# TSOC_GROVEY_WIFI_R1_0.net
KiCad netlist of a schematic drawn in EAGLE
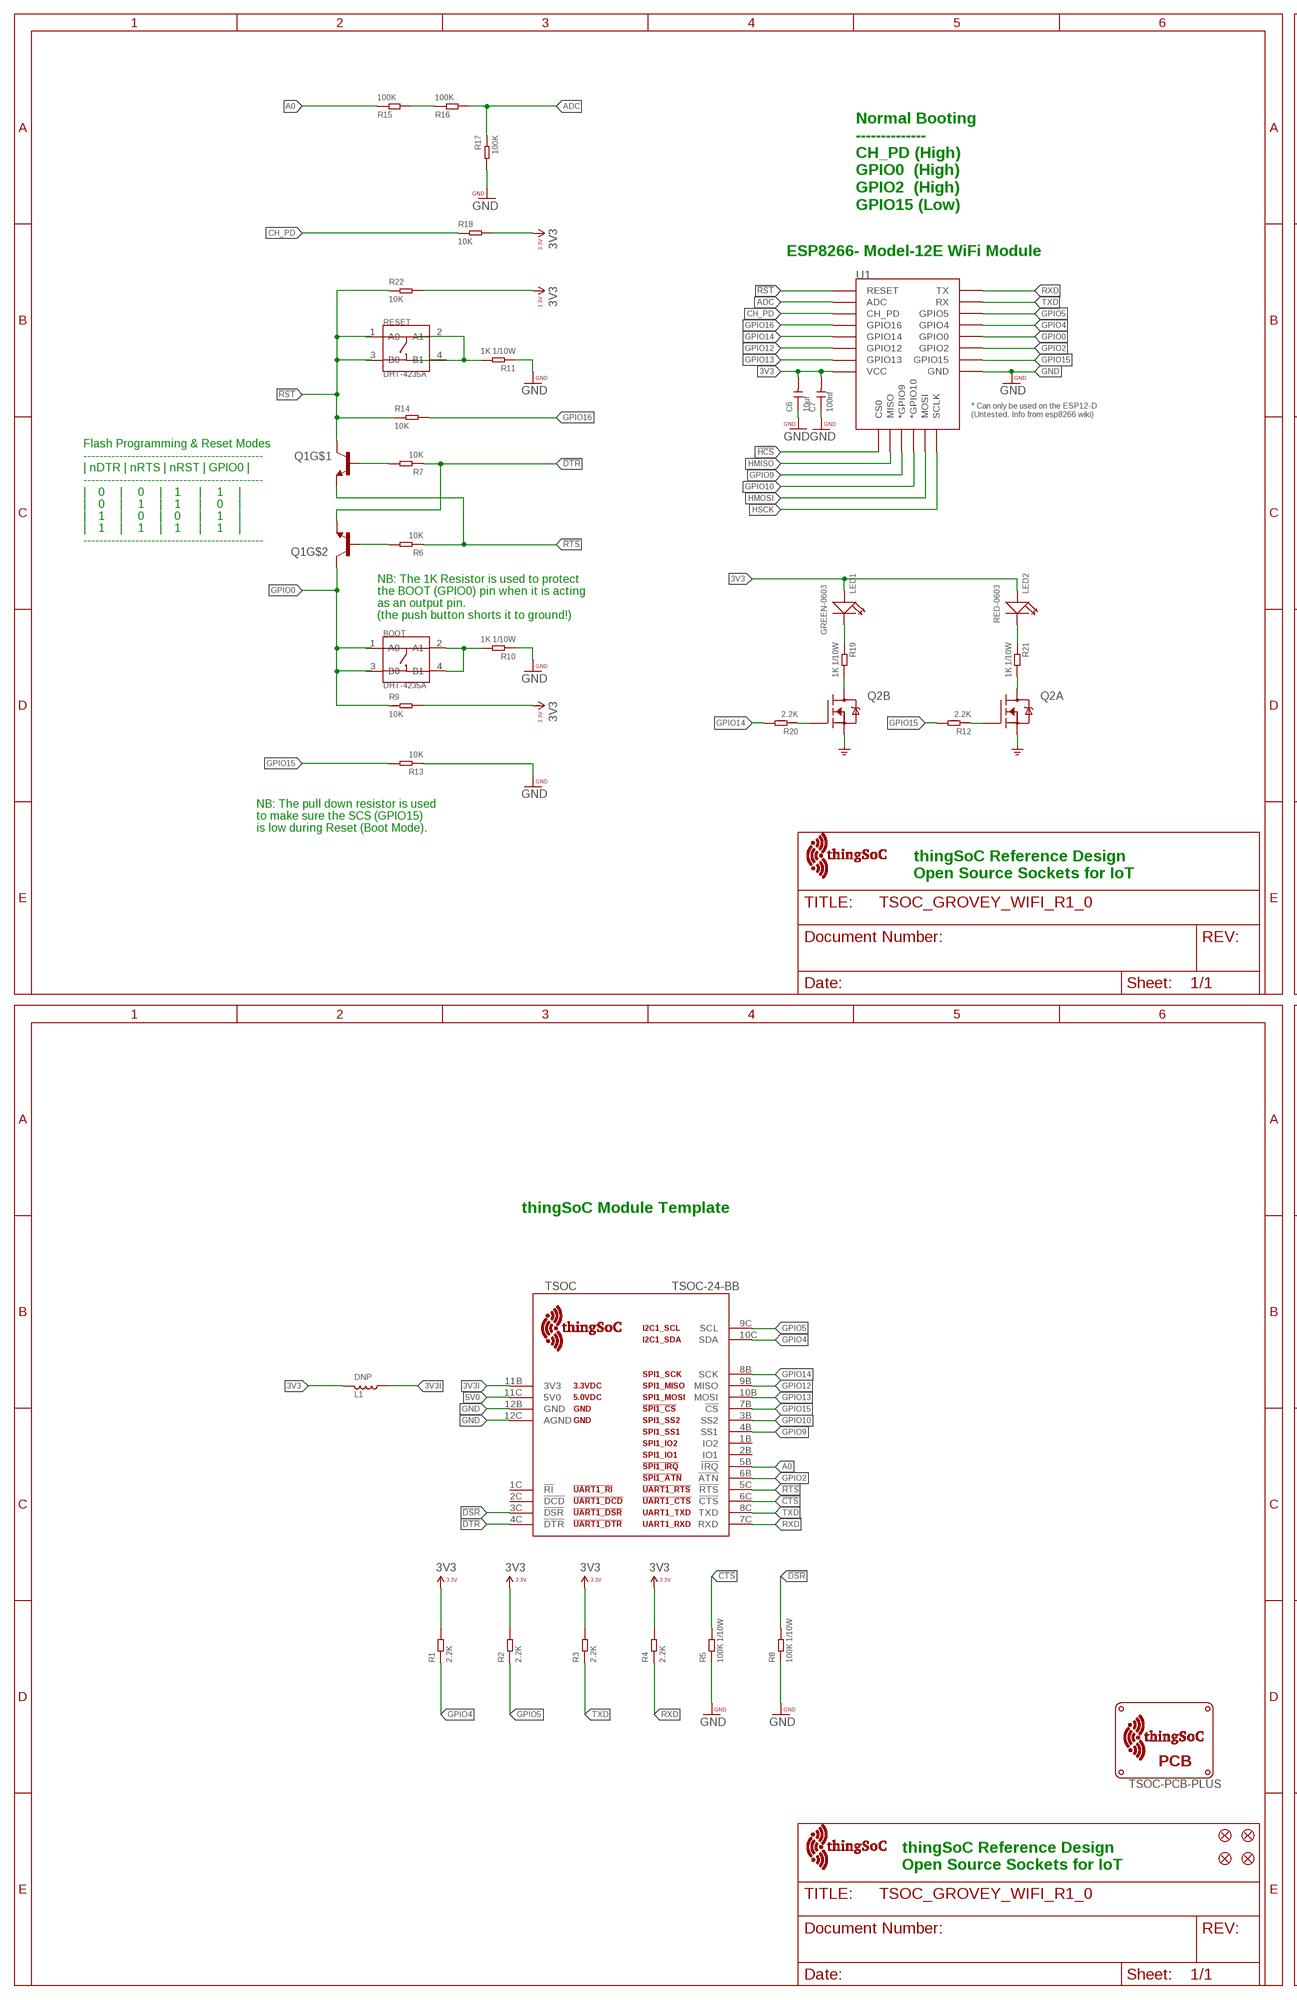
[diagram p0: schematic, sheet 1, part 1 of 2]
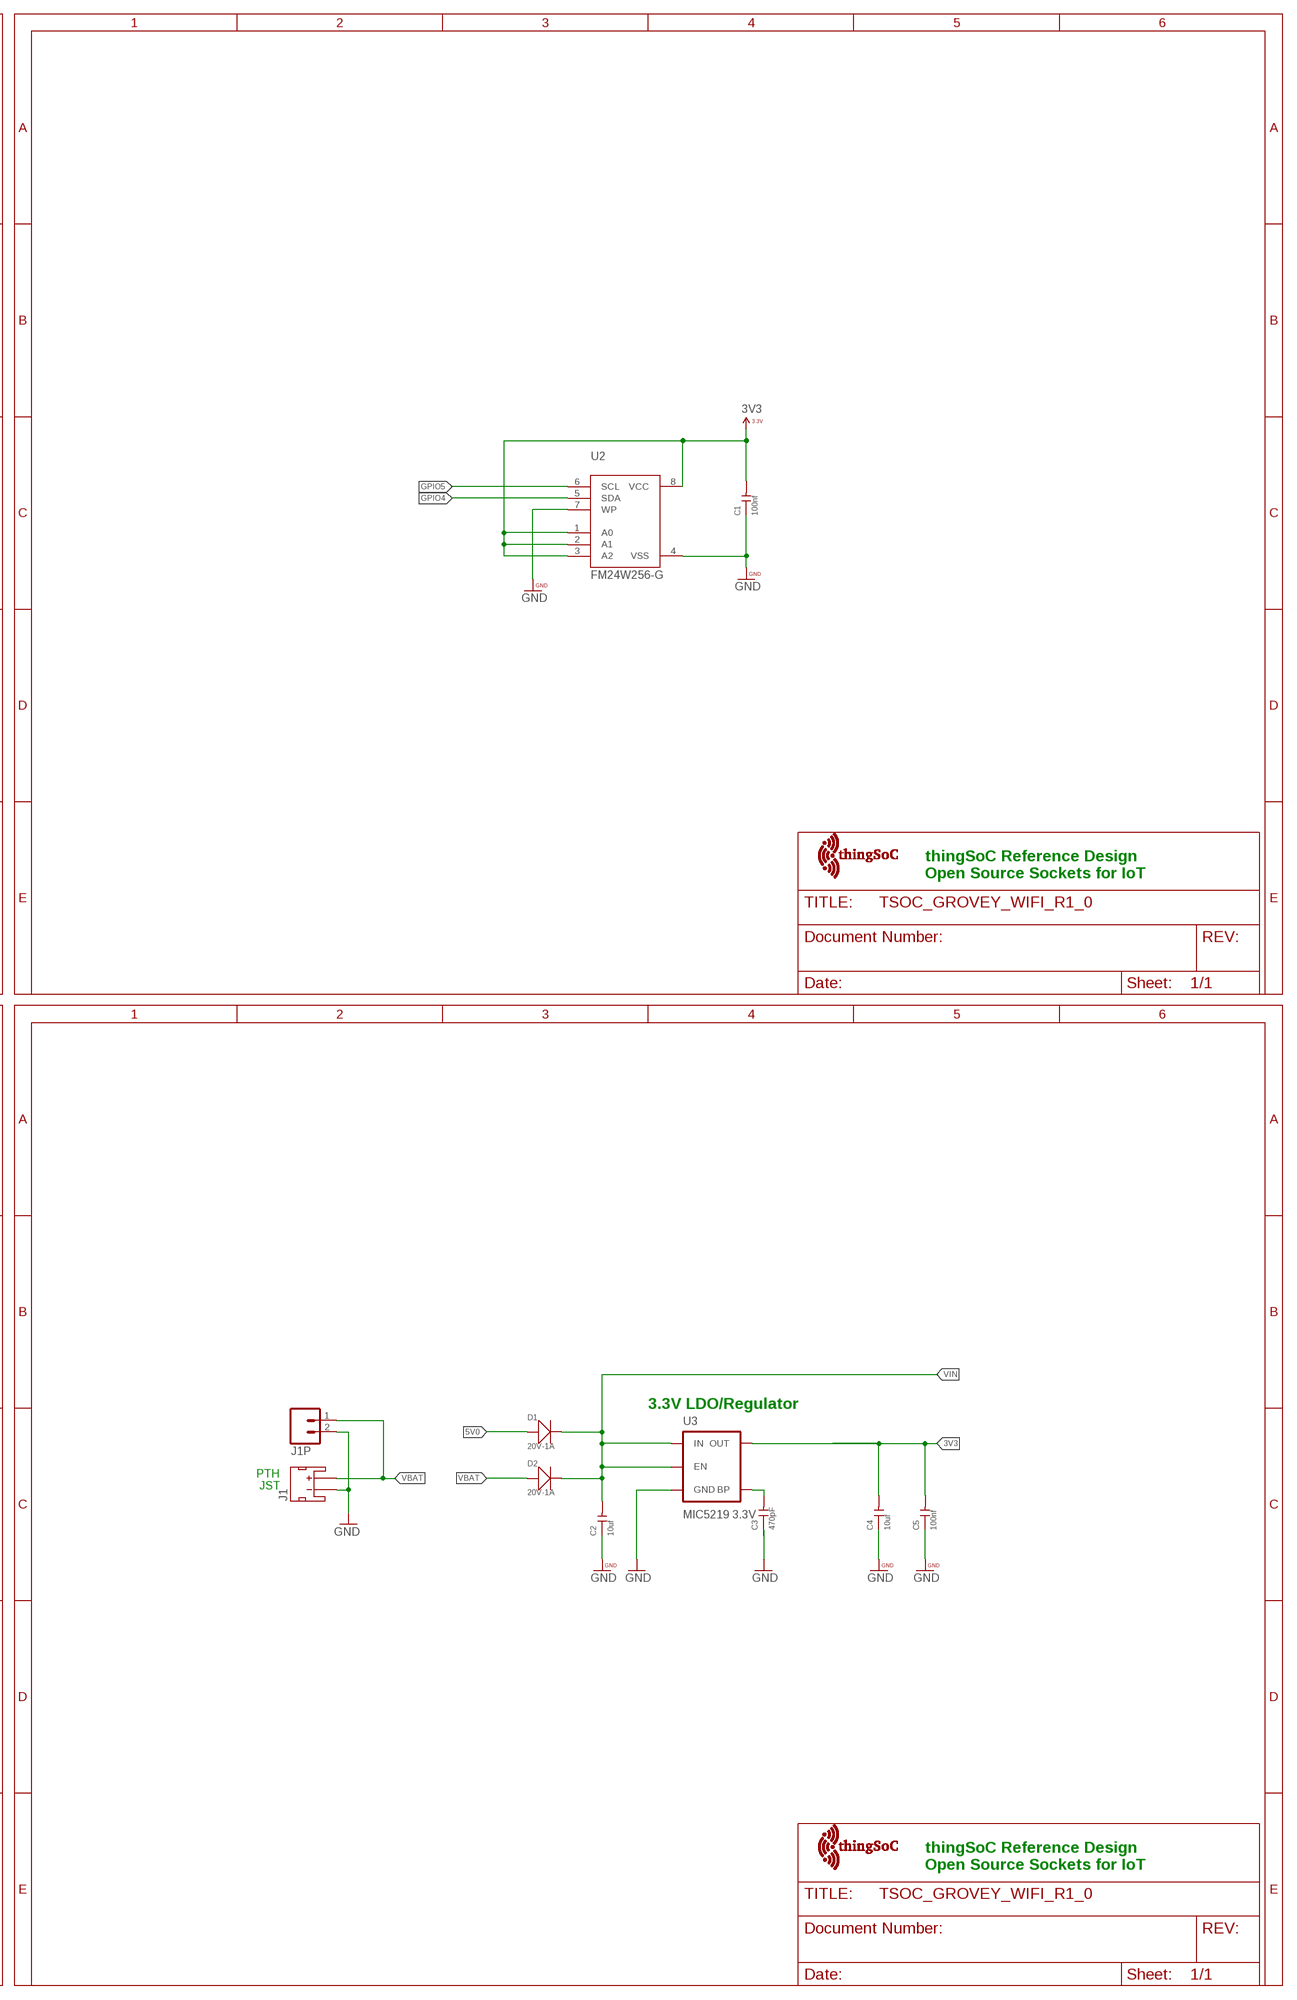
[diagram p1: schematic, sheet 1, part 2 of 2]

(export (version "E")
  (design (tool "Eeschema 10.0.6"))
  (components
    (comp (ref "$$U$1")
      (value "TSOC-LOGO-MED")
      (footprint "eagle-import:TSOC-LOGO-MED")
      (libsource (lib "eagle-import") (part "TSOC-LOGO-MED"))
    )
    (comp (ref "$$U$2")
      (value "TSOC-LOGO-MED")
      (footprint "eagle-import:TSOC-LOGO-MED")
      (libsource (lib "eagle-import") (part "TSOC-LOGO-MED"))
    )
    (comp (ref "BOOT")
      (value "DHT-4235A")
      (footprint "eagle-import:SW4-SMD-4.2X3.2X2.5MM")
      (libsource (lib "eagle-import") (part "SMD-BUTTON-TOP-DHT-4235A(4P-4.2X3.2MM)"))
    )
    (comp (ref "C1")
      (value "100nf")
      (footprint "eagle-import:C0603")
      (fields (field (name "MPN") "CC0603KRX7R9BB104"))
      (libsource (lib "eagle-import") (part "CERAMIC-100NF-50V-10%-X7R(0603)"))
    )
    (comp (ref "C2")
      (value "10uf")
      (footprint "eagle-import:C1206")
      (fields (field (name "MPN") "CC1206KKX5R8BB106"))
      (libsource (lib "eagle-import") (part "CERAMIC-10UF-25V-10%-X5R(1206)"))
    )
    (comp (ref "C3")
      (value "470pF")
      (footprint "eagle-import:C0603")
      (fields (field (name "MPN") "CC0603KRX7R9BB104"))
      (libsource (lib "eagle-import") (part "CERAMIC-100NF-50V-10%-X7R(0603)"))
    )
    (comp (ref "C4")
      (value "10uf")
      (footprint "eagle-import:C1206")
      (fields (field (name "MPN") "CC1206KKX5R8BB106"))
      (libsource (lib "eagle-import") (part "CERAMIC-10UF-25V-10%-X5R(1206)"))
    )
    (comp (ref "C5")
      (value "100nf")
      (footprint "eagle-import:C0603")
      (fields (field (name "MPN") "CC0603KRX7R9BB104"))
      (libsource (lib "eagle-import") (part "CERAMIC-100NF-50V-10%-X7R(0603)"))
    )
    (comp (ref "C6")
      (value "10uf")
      (footprint "eagle-import:C1206")
      (fields (field (name "MPN") "CC1206KKX5R8BB106"))
      (libsource (lib "eagle-import") (part "CERAMIC-10UF-25V-10%-X5R(1206)"))
    )
    (comp (ref "C7")
      (value "100nf")
      (footprint "eagle-import:C0603")
      (fields (field (name "MPN") "CC0603KRX7R9BB104"))
      (libsource (lib "eagle-import") (part "CERAMIC-100NF-50V-10%-X7R(0603)"))
    )
    (comp (ref "D1")
      (value "20V-1A")
      (footprint "eagle-import:SOD-123")
      (fields (field (name "MPN") "B5819W"))
      (libsource (lib "eagle-import") (part "SMD-DIODE-SCHOTTKY-20V-1A(SOD-123)"))
    )
    (comp (ref "D2")
      (value "20V-1A")
      (footprint "eagle-import:SOD-123")
      (fields (field (name "MPN") "B5819W"))
      (libsource (lib "eagle-import") (part "SMD-DIODE-SCHOTTKY-20V-1A(SOD-123)"))
    )
    (comp (ref "FID1")
      (value "FIDUCIALUFIDUCIAL")
      (footprint "eagle-import:MICRO-FIDUCIAL")
      (libsource (lib "eagle-import") (part "FIDUCIALUFIDUCIAL"))
    )
    (comp (ref "FID2")
      (value "FIDUCIALUFIDUCIAL")
      (footprint "eagle-import:MICRO-FIDUCIAL")
      (libsource (lib "eagle-import") (part "FIDUCIALUFIDUCIAL"))
    )
    (comp (ref "FID3")
      (value "FIDUCIALUFIDUCIAL")
      (footprint "eagle-import:MICRO-FIDUCIAL")
      (libsource (lib "eagle-import") (part "FIDUCIALUFIDUCIAL"))
    )
    (comp (ref "FID4")
      (value "FIDUCIALUFIDUCIAL")
      (footprint "eagle-import:MICRO-FIDUCIAL")
      (libsource (lib "eagle-import") (part "FIDUCIALUFIDUCIAL"))
    )
    (comp (ref "J1")
      (value "JST_2MM_MALE")
      (footprint "eagle-import:JST-2-SMD")
      (libsource (lib "eagle-import") (part "JST_2MM_MALE"))
    )
    (comp (ref "J1P")
      (value "M02-JST-2-PTH-NO_SILK")
      (footprint "eagle-import:JST-2-PTH-NS")
      (libsource (lib "eagle-import") (part "M02-JST-2-PTH-NO_SILK"))
    )
    (comp (ref "L1")
      (value "DNP")
      (footprint "eagle-import:L0603")
      (fields (field (name "MPN") "BLM18AG121SN1D"))
      (libsource (lib "eagle-import") (part "SMD-FERRITE-CHIP-120-OHM-500MA(0603)"))
    )
    (comp (ref "LED1")
      (value "GREEN-0603")
      (footprint "eagle-import:LED-0603")
      (fields (field (name "MPN") "19-217-G7C-AN1P2-3T"))
      (libsource (lib "eagle-import") (part "SMD-LED-CLEAR-GREEN(0603)"))
    )
    (comp (ref "LED2")
      (value "RED-0603")
      (footprint "eagle-import:LED-0603")
      (fields (field (name "MPN") "19-217-R6C-AL1M2VY-3T"))
      (libsource (lib "eagle-import") (part "LED-SMD-RED-DIFFUSED(0603)"))
    )
    (comp (ref "PCB")
      (value "TSOC-PCB-PLUS")
      (footprint "eagle-import:TSOC-BB-BRD-PLUS-DIM")
      (libsource (lib "eagle-import") (part "TSOC-PCB-PLUS"))
    )
    (comp (ref "Q1")
      (value "MMBT2222A")
      (footprint "eagle-import:SOT363")
      (libsource (lib "eagle-import") (part "MMDT3904"))
    )
    (comp (ref "Q2")
      (value "FDG1024NZ")
      (footprint "eagle-import:SOT95P280X110-6N")
      (libsource (lib "eagle-import") (part "FDG1024NZ"))
    )
    (comp (ref "R1")
      (value "2.2K")
      (footprint "eagle-import:R0603")
      (fields (field (name "MPN") "RC0603JR-072K2L"))
      (libsource (lib "eagle-import") (part "SMD-RES-2.2K-5%-1/10W(0603)"))
    )
    (comp (ref "R2")
      (value "2.2K")
      (footprint "eagle-import:R0603")
      (fields (field (name "MPN") "RC0603JR-072K2L"))
      (libsource (lib "eagle-import") (part "SMD-RES-2.2K-5%-1/10W(0603)"))
    )
    (comp (ref "R3")
      (value "2.2K")
      (footprint "eagle-import:R0603")
      (fields (field (name "MPN") "RC0603JR-072K2L"))
      (libsource (lib "eagle-import") (part "SMD-RES-2.2K-5%-1/10W(0603)"))
    )
    (comp (ref "R4")
      (value "2.2K")
      (footprint "eagle-import:R0603")
      (fields (field (name "MPN") "RC0603JR-072K2L"))
      (libsource (lib "eagle-import") (part "SMD-RES-2.2K-5%-1/10W(0603)"))
    )
    (comp (ref "R5")
      (value "100K 1/10W")
      (footprint "eagle-import:R0603")
      (fields (field (name "MPN") "RC0603JR-07100KL"))
      (libsource (lib "eagle-import") (part "SMD-RES-100K-5%-1/10W(0603)"))
    )
    (comp (ref "R6")
      (value "10K")
      (footprint "eagle-import:R0603")
      (fields (field (name "MPN") "RC0603FR-0710KL"))
      (libsource (lib "eagle-import") (part "SMD-RES-10K-1%-1/10W(0603)"))
    )
    (comp (ref "R7")
      (value "10K")
      (footprint "eagle-import:R0603")
      (fields (field (name "MPN") "RC0603FR-0710KL"))
      (libsource (lib "eagle-import") (part "SMD-RES-10K-1%-1/10W(0603)"))
    )
    (comp (ref "R8")
      (value "100K 1/10W")
      (footprint "eagle-import:R0603")
      (fields (field (name "MPN") "RC0603JR-07100KL"))
      (libsource (lib "eagle-import") (part "SMD-RES-100K-5%-1/10W(0603)"))
    )
    (comp (ref "R9")
      (value "10K")
      (footprint "eagle-import:R0603")
      (fields (field (name "MPN") "RC0603FR-0710KL"))
      (libsource (lib "eagle-import") (part "SMD-RES-10K-1%-1/10W(0603)"))
    )
    (comp (ref "R10")
      (value "1K 1/10W")
      (footprint "eagle-import:R0603")
      (fields (field (name "MPN") "RC0603JR-071KL"))
      (libsource (lib "eagle-import") (part "SMD-RES-1K-5%-1/10W(0603)"))
    )
    (comp (ref "R11")
      (value "1K 1/10W")
      (footprint "eagle-import:R0603")
      (fields (field (name "MPN") "RC0603JR-071KL"))
      (libsource (lib "eagle-import") (part "SMD-RES-1K-5%-1/10W(0603)"))
    )
    (comp (ref "R12")
      (value "2.2K")
      (footprint "eagle-import:R0603")
      (fields (field (name "MPN") "RC0603JR-072K2L"))
      (libsource (lib "eagle-import") (part "SMD-RES-2.2K-5%-1/10W(0603)"))
    )
    (comp (ref "R13")
      (value "10K")
      (footprint "eagle-import:R0603")
      (fields (field (name "MPN") "RC0603FR-0710KL"))
      (libsource (lib "eagle-import") (part "SMD-RES-10K-1%-1/10W(0603)"))
    )
    (comp (ref "R14")
      (value "10K")
      (footprint "eagle-import:R0603")
      (fields (field (name "MPN") "RC0603FR-0710KL"))
      (libsource (lib "eagle-import") (part "SMD-RES-10K-1%-1/10W(0603)"))
    )
    (comp (ref "R15")
      (value "100K")
      (footprint "eagle-import:R0603")
      (fields (field (name "MPN") "RC0603FR-07100KL"))
      (libsource (lib "eagle-import") (part "SMD-RES-100K-1%-1/10W(0603)"))
    )
    (comp (ref "R16")
      (value "100K")
      (footprint "eagle-import:R0603")
      (fields (field (name "MPN") "RC0603FR-07100KL"))
      (libsource (lib "eagle-import") (part "SMD-RES-100K-1%-1/10W(0603)"))
    )
    (comp (ref "R17")
      (value "100K")
      (footprint "eagle-import:R0603")
      (fields (field (name "MPN") "RC0603FR-07100KL"))
      (libsource (lib "eagle-import") (part "SMD-RES-100K-1%-1/10W(0603)"))
    )
    (comp (ref "R18")
      (value "10K")
      (footprint "eagle-import:R0603")
      (fields (field (name "MPN") "RC0603FR-0710KL"))
      (libsource (lib "eagle-import") (part "SMD-RES-10K-1%-1/10W(0603)"))
    )
    (comp (ref "R19")
      (value "1K 1/10W")
      (footprint "eagle-import:R0603")
      (fields (field (name "MPN") "RC0603JR-071KL"))
      (libsource (lib "eagle-import") (part "SMD-RES-1K-5%-1/10W(0603)"))
    )
    (comp (ref "R20")
      (value "2.2K")
      (footprint "eagle-import:R0603")
      (fields (field (name "MPN") "RC0603JR-072K2L"))
      (libsource (lib "eagle-import") (part "SMD-RES-2.2K-5%-1/10W(0603)"))
    )
    (comp (ref "R21")
      (value "1K 1/10W")
      (footprint "eagle-import:R0603")
      (fields (field (name "MPN") "RC0603JR-071KL"))
      (libsource (lib "eagle-import") (part "SMD-RES-1K-5%-1/10W(0603)"))
    )
    (comp (ref "R22")
      (value "10K")
      (footprint "eagle-import:R0603")
      (fields (field (name "MPN") "RC0603FR-0710KL"))
      (libsource (lib "eagle-import") (part "SMD-RES-10K-1%-1/10W(0603)"))
    )
    (comp (ref "RESET")
      (value "DHT-4235A")
      (footprint "eagle-import:SW4-SMD-4.2X3.2X2.5MM")
      (libsource (lib "eagle-import") (part "SMD-BUTTON-TOP-DHT-4235A(4P-4.2X3.2MM)"))
    )
    (comp (ref "TSOC")
      (value "TSOC-24-BB")
      (footprint "eagle-import:TSOC-BB-S24")
      (libsource (lib "eagle-import") (part "TSOC-24-BB"))
    )
    (comp (ref "U$101")
      (value "TSOC-LOGO-MED")
      (footprint "eagle-import:TSOC-LOGO-MED")
      (libsource (lib "eagle-import") (part "TSOC-LOGO-MED"))
    )
    (comp (ref "U$102")
      (value "TSOC-LOGO-MED")
      (footprint "eagle-import:TSOC-LOGO-MED")
      (libsource (lib "eagle-import") (part "TSOC-LOGO-MED"))
    )
    (comp (ref "U1")
      (value "ESP12ESMD")
      (footprint "eagle-import:ESP12E-SMD")
      (libsource (lib "eagle-import") (part "ESP12ESMD"))
    )
    (comp (ref "U2")
      (value "FM24W256-G")
      (footprint "eagle-import:SO08")
      (libsource (lib "eagle-import") (part "FM24W256-G"))
    )
    (comp (ref "U3")
      (value "MIC5219 3.3V")
      (footprint "eagle-import:SOT23-5")
      (libsource (lib "eagle-import") (part "V_REG_MIC52193.3V"))
    )
  )
  (nets
    (net (code "1") (name "/~{CTS}") (class "Default")
      (node (ref "R5") (pin "2") (pinfunction "2_2") (pintype "passive"))
      (node (ref "TSOC") (pin "6C") (pinfunction "~{CTS}_6C") (pintype "bidirectional"))
    )
    (net (code "2") (name "/~{DSR}") (class "Default")
      (node (ref "R8") (pin "2") (pinfunction "2_2") (pintype "passive"))
      (node (ref "TSOC") (pin "3C") (pinfunction "~{DSR}_3C") (pintype "bidirectional"))
    )
    (net (code "3") (name "/~{DTR}") (class "Default")
      (node (ref "Q1") (pin "1") (pinfunction "E_1") (pintype "passive"))
      (node (ref "R7") (pin "1") (pinfunction "1_1") (pintype "passive"))
      (node (ref "TSOC") (pin "4C") (pinfunction "~{DTR}_4C") (pintype "bidirectional"))
    )
    (net (code "4") (name "/~{HCS}") (class "Default")
      (node (ref "U1") (pin "CS0") (pinfunction "CS0_CS0") (pintype "bidirectional"))
    )
    (net (code "5") (name "/~{RST}") (class "Default")
      (node (ref "Q1") (pin "3") (pinfunction "C_3") (pintype "passive"))
      (node (ref "R14") (pin "1") (pinfunction "1_1") (pintype "passive"))
      (node (ref "R22") (pin "1") (pinfunction "1_1") (pintype "passive"))
      (node (ref "RESET") (pin "1") (pinfunction "A0_1") (pintype "bidirectional"))
      (node (ref "RESET") (pin "3") (pinfunction "B0_3") (pintype "bidirectional"))
      (node (ref "U1") (pin "RESET") (pinfunction "RESET_RESET") (pintype "bidirectional"))
    )
    (net (code "6") (name "/~{RTS}") (class "Default")
      (node (ref "Q1") (pin "4") (pinfunction "E_4") (pintype "passive"))
      (node (ref "R6") (pin "1") (pinfunction "1_1") (pintype "passive"))
      (node (ref "TSOC") (pin "5C") (pinfunction "~{RTS}_5C") (pintype "bidirectional"))
    )
    (net (code "7") (name "3V3") (class "Default")
      (node (ref "C1") (pin "2") (pinfunction "2_2") (pintype "passive"))
      (node (ref "C4") (pin "2") (pinfunction "2_2") (pintype "passive"))
      (node (ref "C5") (pin "2") (pinfunction "2_2") (pintype "passive"))
      (node (ref "C6") (pin "2") (pinfunction "2_2") (pintype "passive"))
      (node (ref "C7") (pin "2") (pinfunction "2_2") (pintype "passive"))
      (node (ref "L1") (pin "1") (pinfunction "1_1") (pintype "passive"))
      (node (ref "LED1") (pin "+") (pinfunction "+_+") (pintype "passive"))
      (node (ref "LED2") (pin "+") (pinfunction "+_+") (pintype "passive"))
      (node (ref "R1") (pin "2") (pinfunction "2_2") (pintype "passive"))
      (node (ref "R18") (pin "2") (pinfunction "2_2") (pintype "passive"))
      (node (ref "R2") (pin "2") (pinfunction "2_2") (pintype "passive"))
      (node (ref "R22") (pin "2") (pinfunction "2_2") (pintype "passive"))
      (node (ref "R3") (pin "2") (pinfunction "2_2") (pintype "passive"))
      (node (ref "R4") (pin "2") (pinfunction "2_2") (pintype "passive"))
      (node (ref "R9") (pin "2") (pinfunction "2_2") (pintype "passive"))
      (node (ref "U1") (pin "VCC") (pinfunction "VCC_VCC") (pintype "bidirectional"))
      (node (ref "U2") (pin "1") (pinfunction "A0_1") (pintype "bidirectional"))
      (node (ref "U2") (pin "2") (pinfunction "A1_2") (pintype "bidirectional"))
      (node (ref "U2") (pin "3") (pinfunction "A2_3") (pintype "bidirectional"))
      (node (ref "U2") (pin "8") (pinfunction "VCC_8") (pintype "power_in"))
      (node (ref "U3") (pin "5") (pinfunction "OUT_5") (pintype "passive"))
    )
    (net (code "8") (name "3V3I") (class "Default")
      (node (ref "L1") (pin "2") (pinfunction "2_2") (pintype "passive"))
      (node (ref "TSOC") (pin "11B") (pinfunction "3V3_11B") (pintype "bidirectional"))
    )
    (net (code "9") (name "5V0") (class "Default")
      (node (ref "D1") (pin "+") (pinfunction "+_+") (pintype "passive"))
      (node (ref "TSOC") (pin "11C") (pinfunction "5V0_11C") (pintype "bidirectional"))
    )
    (net (code "10") (name "A0") (class "Default")
      (node (ref "R15") (pin "1") (pinfunction "1_1") (pintype "passive"))
      (node (ref "TSOC") (pin "5B") (pinfunction "~{IRQ}_5B") (pintype "bidirectional"))
    )
    (net (code "11") (name "ADC") (class "Default")
      (node (ref "R16") (pin "2") (pinfunction "2_2") (pintype "passive"))
      (node (ref "R17") (pin "1") (pinfunction "1_1") (pintype "passive"))
      (node (ref "U1") (pin "ADC") (pinfunction "ADC_ADC") (pintype "bidirectional"))
    )
    (net (code "12") (name "CH_PD") (class "Default")
      (node (ref "R18") (pin "1") (pinfunction "1_1") (pintype "passive"))
      (node (ref "U1") (pin "CH_PD") (pinfunction "CH_PD_CH_PD") (pintype "bidirectional"))
    )
    (net (code "13") (name "GND") (class "Default")
      (node (ref "C1") (pin "1") (pinfunction "1_1") (pintype "passive"))
      (node (ref "C2") (pin "1") (pinfunction "1_1") (pintype "passive"))
      (node (ref "C3") (pin "1") (pinfunction "1_1") (pintype "passive"))
      (node (ref "C4") (pin "1") (pinfunction "1_1") (pintype "passive"))
      (node (ref "C5") (pin "1") (pinfunction "1_1") (pintype "passive"))
      (node (ref "C6") (pin "1") (pinfunction "1_1") (pintype "passive"))
      (node (ref "C7") (pin "1") (pinfunction "1_1") (pintype "passive"))
      (node (ref "J1") (pin "1") (pinfunction "-_1") (pintype "bidirectional"))
      (node (ref "J1P") (pin "2") (pinfunction "2_2") (pintype "passive"))
      (node (ref "Q2") (pin "1") (pinfunction "S_1") (pintype "passive"))
      (node (ref "Q2") (pin "4") (pinfunction "S_4") (pintype "passive"))
      (node (ref "R10") (pin "1") (pinfunction "1_1") (pintype "passive"))
      (node (ref "R11") (pin "1") (pinfunction "1_1") (pintype "passive"))
      (node (ref "R13") (pin "1") (pinfunction "1_1") (pintype "passive"))
      (node (ref "R17") (pin "2") (pinfunction "2_2") (pintype "passive"))
      (node (ref "R5") (pin "1") (pinfunction "1_1") (pintype "passive"))
      (node (ref "R8") (pin "1") (pinfunction "1_1") (pintype "passive"))
      (node (ref "TSOC") (pin "12B") (pinfunction "GND_12B") (pintype "bidirectional"))
      (node (ref "TSOC") (pin "12C") (pinfunction "AGND_12C") (pintype "bidirectional"))
      (node (ref "U1") (pin "GND") (pinfunction "GND_GND") (pintype "bidirectional"))
      (node (ref "U2") (pin "4") (pinfunction "VSS_4") (pintype "power_in"))
      (node (ref "U2") (pin "7") (pinfunction "WP_7") (pintype "bidirectional"))
      (node (ref "U3") (pin "2") (pinfunction "GND_2") (pintype "input"))
    )
    (net (code "14") (name "GPIO0") (class "Default")
      (node (ref "BOOT") (pin "1") (pinfunction "A0_1") (pintype "bidirectional"))
      (node (ref "BOOT") (pin "3") (pinfunction "B0_3") (pintype "bidirectional"))
      (node (ref "Q1") (pin "6") (pinfunction "C_6") (pintype "passive"))
      (node (ref "R9") (pin "1") (pinfunction "1_1") (pintype "passive"))
      (node (ref "U1") (pin "GPIO0") (pinfunction "GPIO0_GPIO0") (pintype "bidirectional"))
    )
    (net (code "15") (name "GPIO2") (class "Default")
      (node (ref "TSOC") (pin "6B") (pinfunction "~{ATN}_6B") (pintype "bidirectional"))
      (node (ref "U1") (pin "GPIO2") (pinfunction "GPIO2_GPIO2") (pintype "bidirectional"))
    )
    (net (code "16") (name "GPIO4") (class "Default")
      (node (ref "R1") (pin "1") (pinfunction "1_1") (pintype "passive"))
      (node (ref "TSOC") (pin "10C") (pinfunction "SDA_10C") (pintype "bidirectional"))
      (node (ref "U1") (pin "GPIO4") (pinfunction "GPIO4_GPIO4") (pintype "bidirectional"))
      (node (ref "U2") (pin "5") (pinfunction "SDA_5") (pintype "bidirectional"))
    )
    (net (code "17") (name "GPIO5") (class "Default")
      (node (ref "R2") (pin "1") (pinfunction "1_1") (pintype "passive"))
      (node (ref "TSOC") (pin "9C") (pinfunction "SCL_9C") (pintype "bidirectional"))
      (node (ref "U1") (pin "GPIO5") (pinfunction "GPIO5_GPIO5") (pintype "bidirectional"))
      (node (ref "U2") (pin "6") (pinfunction "SCL_6") (pintype "bidirectional"))
    )
    (net (code "18") (name "GPIO9") (class "Default")
      (node (ref "TSOC") (pin "4B") (pinfunction "SS1_4B") (pintype "bidirectional"))
      (node (ref "U1") (pin "GPIO9") (pinfunction "*GPIO9_GPIO9") (pintype "bidirectional"))
    )
    (net (code "19") (name "GPIO10") (class "Default")
      (node (ref "TSOC") (pin "3B") (pinfunction "SS2_3B") (pintype "bidirectional"))
      (node (ref "U1") (pin "GPIO10") (pinfunction "*GPIO10_GPIO10") (pintype "bidirectional"))
    )
    (net (code "20") (name "GPIO12") (class "Default")
      (node (ref "TSOC") (pin "9B") (pinfunction "MISO_9B") (pintype "bidirectional"))
      (node (ref "U1") (pin "GPIO12") (pinfunction "GPIO12_GPIO12") (pintype "bidirectional"))
    )
    (net (code "21") (name "GPIO13") (class "Default")
      (node (ref "TSOC") (pin "10B") (pinfunction "MOSI_10B") (pintype "bidirectional"))
      (node (ref "U1") (pin "GPIO13") (pinfunction "GPIO13_GPIO13") (pintype "bidirectional"))
    )
    (net (code "22") (name "GPIO14") (class "Default")
      (node (ref "R20") (pin "2") (pinfunction "2_2") (pintype "passive"))
      (node (ref "TSOC") (pin "8B") (pinfunction "SCK_8B") (pintype "bidirectional"))
      (node (ref "U1") (pin "GPIO14") (pinfunction "GPIO14_GPIO14") (pintype "bidirectional"))
    )
    (net (code "23") (name "GPIO15") (class "Default")
      (node (ref "R12") (pin "2") (pinfunction "2_2") (pintype "passive"))
      (node (ref "R13") (pin "2") (pinfunction "2_2") (pintype "passive"))
      (node (ref "TSOC") (pin "7B") (pinfunction "~{CS}_7B") (pintype "bidirectional"))
      (node (ref "U1") (pin "GPIO15") (pinfunction "GPIO15_GPIO15") (pintype "bidirectional"))
    )
    (net (code "24") (name "GPIO16") (class "Default")
      (node (ref "R14") (pin "2") (pinfunction "2_2") (pintype "passive"))
      (node (ref "U1") (pin "GPIO16") (pinfunction "GPIO16_GPIO16") (pintype "bidirectional"))
    )
    (net (code "25") (name "HMISO") (class "Default")
      (node (ref "U1") (pin "MISO") (pinfunction "MISO_MISO") (pintype "bidirectional"))
    )
    (net (code "26") (name "HMOSI") (class "Default")
      (node (ref "U1") (pin "MOSI") (pinfunction "MOSI_MOSI") (pintype "bidirectional"))
    )
    (net (code "27") (name "HSCK") (class "Default")
      (node (ref "U1") (pin "SCLK") (pinfunction "SCLK_SCLK") (pintype "bidirectional"))
    )
    (net (code "28") (name "Net-(BOOT-A1)") (class "Default")
      (node (ref "BOOT") (pin "2") (pinfunction "A1_2") (pintype "bidirectional"))
      (node (ref "BOOT") (pin "4") (pinfunction "B1_4") (pintype "bidirectional"))
      (node (ref "R10") (pin "2") (pinfunction "2_2") (pintype "passive"))
    )
    (net (code "29") (name "Net-(LED1-Pad-)") (class "Default")
      (node (ref "LED1") (pin "-") (pinfunction "-_-") (pintype "passive"))
      (node (ref "R19") (pin "1") (pinfunction "1_1") (pintype "passive"))
    )
    (net (code "30") (name "Net-(LED2-Pad-)") (class "Default")
      (node (ref "LED2") (pin "-") (pinfunction "-_-") (pintype "passive"))
      (node (ref "R21") (pin "1") (pinfunction "1_1") (pintype "passive"))
    )
    (net (code "31") (name "Net-(Q1A-B)") (class "Default")
      (node (ref "Q1") (pin "5") (pinfunction "B_5") (pintype "passive"))
      (node (ref "R7") (pin "2") (pinfunction "2_2") (pintype "passive"))
    )
    (net (code "32") (name "Net-(Q1B-B)") (class "Default")
      (node (ref "Q1") (pin "2") (pinfunction "B_2") (pintype "passive"))
      (node (ref "R6") (pin "2") (pinfunction "2_2") (pintype "passive"))
    )
    (net (code "33") (name "Net-(Q2A-D)") (class "Default")
      (node (ref "Q2") (pin "6") (pinfunction "D_6") (pintype "passive"))
      (node (ref "R21") (pin "2") (pinfunction "2_2") (pintype "passive"))
    )
    (net (code "34") (name "Net-(Q2A-G)") (class "Default")
      (node (ref "Q2") (pin "2") (pinfunction "G_2") (pintype "passive"))
      (node (ref "R12") (pin "1") (pinfunction "1_1") (pintype "passive"))
    )
    (net (code "35") (name "Net-(Q2B-D)") (class "Default")
      (node (ref "Q2") (pin "3") (pinfunction "D_3") (pintype "passive"))
      (node (ref "R19") (pin "2") (pinfunction "2_2") (pintype "passive"))
    )
    (net (code "36") (name "Net-(Q2B-G)") (class "Default")
      (node (ref "Q2") (pin "5") (pinfunction "G_5") (pintype "passive"))
      (node (ref "R20") (pin "1") (pinfunction "1_1") (pintype "passive"))
    )
    (net (code "37") (name "Net-(R15-Pad2)") (class "Default")
      (node (ref "R15") (pin "2") (pinfunction "2_2") (pintype "passive"))
      (node (ref "R16") (pin "1") (pinfunction "1_1") (pintype "passive"))
    )
    (net (code "38") (name "Net-(RESET-A1)") (class "Default")
      (node (ref "R11") (pin "2") (pinfunction "2_2") (pintype "passive"))
      (node (ref "RESET") (pin "2") (pinfunction "A1_2") (pintype "bidirectional"))
      (node (ref "RESET") (pin "4") (pinfunction "B1_4") (pintype "bidirectional"))
    )
    (net (code "39") (name "Net-(U3-BP)") (class "Default")
      (node (ref "C3") (pin "2") (pinfunction "2_2") (pintype "passive"))
      (node (ref "U3") (pin "4") (pinfunction "BP_4") (pintype "input"))
    )
    (net (code "40") (name "RXD") (class "Default")
      (node (ref "R4") (pin "1") (pinfunction "1_1") (pintype "passive"))
      (node (ref "TSOC") (pin "7C") (pinfunction "RXD_7C") (pintype "bidirectional"))
      (node (ref "U1") (pin "TXD0") (pinfunction "TX_TXD0") (pintype "bidirectional"))
    )
    (net (code "41") (name "TXD") (class "Default")
      (node (ref "R3") (pin "1") (pinfunction "1_1") (pintype "passive"))
      (node (ref "TSOC") (pin "8C") (pinfunction "TXD_8C") (pintype "bidirectional"))
      (node (ref "U1") (pin "RXD0") (pinfunction "RX_RXD0") (pintype "bidirectional"))
    )
    (net (code "42") (name "VBAT") (class "Default")
      (node (ref "D2") (pin "+") (pinfunction "+_+") (pintype "passive"))
      (node (ref "J1") (pin "2") (pinfunction "+_2") (pintype "bidirectional"))
      (node (ref "J1P") (pin "1") (pinfunction "1_1") (pintype "passive"))
    )
    (net (code "43") (name "VIN") (class "Default")
      (node (ref "C2") (pin "2") (pinfunction "2_2") (pintype "passive"))
      (node (ref "D1") (pin "-") (pinfunction "-_-") (pintype "passive"))
      (node (ref "D2") (pin "-") (pinfunction "-_-") (pintype "passive"))
      (node (ref "U3") (pin "1") (pinfunction "IN_1") (pintype "input"))
      (node (ref "U3") (pin "3") (pinfunction "EN_3") (pintype "input"))
    )
    (net (code "44") (name "unconnected-(J1-PAD1-PadNC1)") (class "Default")
      (node (ref "J1") (pin "NC1") (pinfunction "PAD1_NC1") (pintype "bidirectional"))
    )
    (net (code "45") (name "unconnected-(J1-PAD2-PadNC2)") (class "Default")
      (node (ref "J1") (pin "NC2") (pinfunction "PAD2_NC2") (pintype "bidirectional"))
    )
    (net (code "46") (name "unconnected-(TSOC-IO1-Pad2B)") (class "Default")
      (node (ref "TSOC") (pin "2B") (pinfunction "IO1_2B") (pintype "bidirectional"))
    )
    (net (code "47") (name "unconnected-(TSOC-IO2-Pad1B)") (class "Default")
      (node (ref "TSOC") (pin "1B") (pinfunction "IO2_1B") (pintype "bidirectional"))
    )
    (net (code "48") (name "unconnected-(TSOC-~{DCD}-Pad2C)") (class "Default")
      (node (ref "TSOC") (pin "2C") (pinfunction "~{DCD}_2C") (pintype "bidirectional"))
    )
    (net (code "49") (name "unconnected-(TSOC-~{RI}-Pad1C)") (class "Default")
      (node (ref "TSOC") (pin "1C") (pinfunction "~{RI}_1C") (pintype "bidirectional"))
    )
  )
)
